# PointMotorBoard.net
KiCad netlist of a schematic drawn in EAGLE
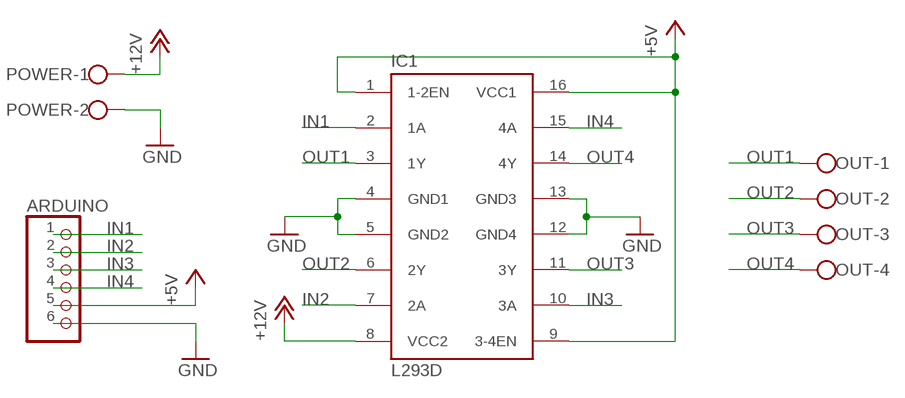
[diagram p0: schematic, sheet 1]

(export (version "E")
  (design (tool "Eeschema 10.0.6"))
  (components
    (comp (ref "ARDUINO")
      (value "PINHD-1X6")
      (footprint "eagle-import:1X06")
      (libsource (lib "eagle-import") (part "PINHD-1X6"))
    )
    (comp (ref "IC1")
      (value "L293D")
      (footprint "eagle-import:DIL16")
      (libsource (lib "eagle-import") (part "L293D"))
    )
    (comp (ref "OUT")
      (value "W237-4")
      (footprint "eagle-import:W237-4")
      (libsource (lib "eagle-import") (part "W237-4"))
    )
    (comp (ref "POWER")
      (value "W237-102")
      (footprint "eagle-import:W237-102")
      (fields (field (name "MPN") "237-102"))
      (libsource (lib "eagle-import") (part "W237-102"))
    )
  )
  (nets
    (net (code "1") (name "+5V") (class "Default")
      (node (ref "ARDUINO") (pin "5") (pinfunction "5_5") (pintype "passive"))
      (node (ref "IC1") (pin "1") (pinfunction "1-2EN_1") (pintype "input"))
      (node (ref "IC1") (pin "16") (pinfunction "VCC1_16") (pintype "power_in"))
      (node (ref "IC1") (pin "9") (pinfunction "3-4EN_9") (pintype "input"))
    )
    (net (code "2") (name "+12V") (class "Default")
      (node (ref "IC1") (pin "8") (pinfunction "VCC2_8") (pintype "power_in"))
      (node (ref "POWER") (pin "1") (pinfunction "KL_1") (pintype "passive"))
    )
    (net (code "3") (name "/IN1") (class "Default")
      (node (ref "ARDUINO") (pin "1") (pinfunction "1_1") (pintype "passive"))
      (node (ref "IC1") (pin "2") (pinfunction "1A_2") (pintype "input"))
    )
    (net (code "4") (name "/IN2") (class "Default")
      (node (ref "ARDUINO") (pin "2") (pinfunction "2_2") (pintype "passive"))
      (node (ref "IC1") (pin "7") (pinfunction "2A_7") (pintype "input"))
    )
    (net (code "5") (name "/IN3") (class "Default")
      (node (ref "ARDUINO") (pin "3") (pinfunction "3_3") (pintype "passive"))
      (node (ref "IC1") (pin "10") (pinfunction "3A_10") (pintype "input"))
    )
    (net (code "6") (name "/IN4") (class "Default")
      (node (ref "ARDUINO") (pin "4") (pinfunction "4_4") (pintype "passive"))
      (node (ref "IC1") (pin "15") (pinfunction "4A_15") (pintype "input"))
    )
    (net (code "7") (name "/OUT1") (class "Default")
      (node (ref "IC1") (pin "3") (pinfunction "1Y_3") (pintype "output"))
      (node (ref "OUT") (pin "1") (pinfunction "KL_1") (pintype "passive"))
    )
    (net (code "8") (name "/OUT2") (class "Default")
      (node (ref "IC1") (pin "6") (pinfunction "2Y_6") (pintype "output"))
      (node (ref "OUT") (pin "2") (pinfunction "KL_2") (pintype "passive"))
    )
    (net (code "9") (name "/OUT3") (class "Default")
      (node (ref "IC1") (pin "11") (pinfunction "3Y_11") (pintype "output"))
      (node (ref "OUT") (pin "3") (pinfunction "KL_3") (pintype "passive"))
    )
    (net (code "10") (name "/OUT4") (class "Default")
      (node (ref "IC1") (pin "14") (pinfunction "4Y_14") (pintype "output"))
      (node (ref "OUT") (pin "4") (pinfunction "KL_4") (pintype "passive"))
    )
    (net (code "11") (name "GND") (class "Default")
      (node (ref "ARDUINO") (pin "6") (pinfunction "6_6") (pintype "passive"))
      (node (ref "IC1") (pin "12") (pinfunction "GND4_12") (pintype "power_in"))
      (node (ref "IC1") (pin "13") (pinfunction "GND3_13") (pintype "power_in"))
      (node (ref "IC1") (pin "4") (pinfunction "GND1_4") (pintype "power_in"))
      (node (ref "IC1") (pin "5") (pinfunction "GND2_5") (pintype "power_in"))
      (node (ref "POWER") (pin "2") (pinfunction "KL_2") (pintype "passive"))
    )
  )
)
